# Band_Pass_Filter.net
KiCad netlist of a schematic drawn in Altium Designer
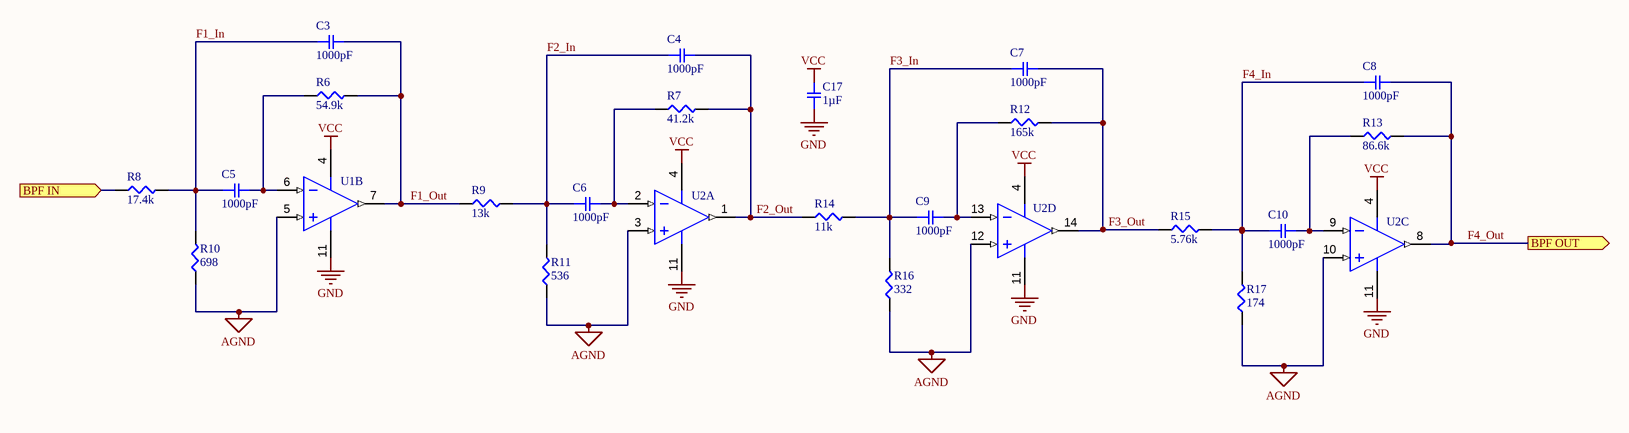
[diagram p0: Band Pass Filter.SchDoc]

(export (version "E")
  (design (tool "Eeschema 10.0.6"))
  (components
    (comp (ref "C3")
      (value "1000pF")
      (footprint "SMD-0603C")
      (description "CAP CER 1000PF 50V X7R 0603")
      (fields
        (field (name "MANUFACTURER") "Walsin Technology Corporation")
        (field (name "MANUFACTURER PART NUMBER") "0603N102F500CT")
      )
      (libsource (lib "capacitor_murata_0603") (part "GCJ188R71H102KA01D"))
    )
    (comp (ref "C4")
      (value "1000pF")
      (footprint "SMD-0603C")
      (description "CAP CER 1000PF 50V X7R 0603")
      (fields
        (field (name "MANUFACTURER") "Walsin Technology Corporation")
        (field (name "MANUFACTURER PART NUMBER") "0603N102F500CT")
      )
      (libsource (lib "capacitor_murata_0603") (part "GCJ188R71H102KA01D"))
    )
    (comp (ref "C5")
      (value "1000pF")
      (footprint "SMD-0603C")
      (description "CAP CER 1000PF 50V X7R 0603")
      (fields
        (field (name "MANUFACTURER") "Walsin Technology Corporation")
        (field (name "MANUFACTURER PART NUMBER") "0603N102F500CT")
      )
      (libsource (lib "capacitor_murata_0603") (part "GCJ188R71H102KA01D"))
    )
    (comp (ref "C6")
      (value "1000pF")
      (footprint "SMD-0603C")
      (description "CAP CER 1000PF 50V X7R 0603")
      (fields
        (field (name "MANUFACTURER") "Walsin Technology Corporation")
        (field (name "MANUFACTURER PART NUMBER") "0603N102F500CT")
      )
      (libsource (lib "capacitor_murata_0603") (part "GCJ188R71H102KA01D"))
    )
    (comp (ref "C7")
      (value "1000pF")
      (footprint "SMD-0603C")
      (description "CAP CER 1000PF 50V X7R 0603")
      (fields
        (field (name "MANUFACTURER") "Walsin Technology Corporation")
        (field (name "MANUFACTURER PART NUMBER") "0603N102F500CT")
      )
      (libsource (lib "capacitor_murata_0603") (part "GCJ188R71H102KA01D"))
    )
    (comp (ref "C8")
      (value "1000pF")
      (footprint "SMD-0603C")
      (description "CAP CER 1000PF 50V X7R 0603")
      (fields
        (field (name "MANUFACTURER") "Walsin Technology Corporation")
        (field (name "MANUFACTURER PART NUMBER") "0603N102F500CT")
      )
      (libsource (lib "capacitor_murata_0603") (part "GCJ188R71H102KA01D"))
    )
    (comp (ref "C9")
      (value "1000pF")
      (footprint "SMD-0603C")
      (description "CAP CER 1000PF 50V X7R 0603")
      (fields
        (field (name "MANUFACTURER") "Walsin Technology Corporation")
        (field (name "MANUFACTURER PART NUMBER") "0603N102F500CT")
      )
      (libsource (lib "capacitor_murata_0603") (part "GCJ188R71H102KA01D"))
    )
    (comp (ref "C10")
      (value "1000pF")
      (footprint "SMD-0603C")
      (description "CAP CER 1000PF 50V X7R 0603")
      (fields
        (field (name "MANUFACTURER") "Walsin Technology Corporation")
        (field (name "MANUFACTURER PART NUMBER") "0603N102F500CT")
      )
      (libsource (lib "capacitor_murata_0603") (part "GCJ188R71H102KA01D"))
    )
    (comp (ref "C17")
      (value "1µF")
      (footprint "SMD-0603C")
      (description "CAP CER 1UF 16V X7R 0603")
      (fields
        (field (name "MANUFACTURER") "Samsung Electro-Mechanics")
        (field (name "MANUFACTURER PART NUMBER") "CL10A105KA8NNNC")
      )
      (libsource (lib "capacitor_murata_0603") (part "GCM188R71C105KA64D"))
    )
    (comp (ref "R6")
      (value "54.9k")
      (footprint "SMD-0603-RES")
      (description "RES SMD 54.9K OHM 1% 1/10W 0603")
      (fields
        (field (name "MANUFACTURER") "Panasonic Electronic Components")
        (field (name "MANUFACTURER PART NUMBER") "ERJ-3EKF5492V")
      )
      (libsource (lib "Panasonic_resistor_0603") (part "ERJ-3EKF5492V"))
    )
    (comp (ref "R7")
      (value "41.2k")
      (footprint "SMD-0603-RES")
      (description "RES SMD 41.2K OHM 1% 1/10W 0603")
      (fields
        (field (name "MANUFACTURER") "Panasonic Electronic Components")
        (field (name "MANUFACTURER PART NUMBER") "ERJ-3EKF4122V")
      )
      (libsource (lib "Panasonic_resistor_0603") (part "ERJ-3EKF4122V"))
    )
    (comp (ref "R8")
      (value "17.4k")
      (footprint "SMD-0603-RES")
      (description "RES SMD 17.4K OHM 1% 1/10W 0603")
      (fields
        (field (name "MANUFACTURER") "Panasonic Electronic Components")
        (field (name "MANUFACTURER PART NUMBER") "ERJ-3EKF1742V")
      )
      (libsource (lib "Panasonic_resistor_0603") (part "ERJ-3EKF1742V"))
    )
    (comp (ref "R9")
      (value "13k")
      (footprint "SMD-0603-RES")
      (description "RES SMD 13K OHM 1% 1/10W 0603")
      (fields
        (field (name "MANUFACTURER") "Panasonic Electronic Components")
        (field (name "MANUFACTURER PART NUMBER") "ERJ-3EKF1302V")
      )
      (libsource (lib "Panasonic_resistor_0603") (part "ERJ-3EKF1302V"))
    )
    (comp (ref "R10")
      (value "698")
      (footprint "SMD-0603-RES")
      (description "RES SMD 698 OHM 1% 1/10W 0603")
      (fields
        (field (name "MANUFACTURER") "Panasonic Electronic Components")
        (field (name "MANUFACTURER PART NUMBER") "ERJ-3EKF6980V")
      )
      (libsource (lib "Panasonic_resistor_0603") (part "ERJ-3EKF6980V"))
    )
    (comp (ref "R11")
      (value "536")
      (footprint "SMD-0603-RES")
      (description "RES SMD 536 OHM 1% 1/10W 0603")
      (fields
        (field (name "MANUFACTURER") "Panasonic Electronic Components")
        (field (name "MANUFACTURER PART NUMBER") "ERJ-3EKF5360V")
      )
      (libsource (lib "Panasonic_resistor_0603") (part "ERJ-3EKF5360V"))
    )
    (comp (ref "R12")
      (value "165k")
      (footprint "SMD-0603-RES")
      (description "RES SMD 165K OHM 1% 1/10W 0603")
      (fields
        (field (name "MANUFACTURER") "Panasonic Electronic Components")
        (field (name "MANUFACTURER PART NUMBER") "ERJ-3EKF1653V")
      )
      (libsource (lib "Panasonic_resistor_0603") (part "ERJ-3EKF1653V"))
    )
    (comp (ref "R13")
      (value "86.6k")
      (footprint "SMD-0603-RES")
      (description "RES SMD 86.6K OHM 1% 1/10W 0603")
      (fields
        (field (name "MANUFACTURER") "Panasonic Electronic Components")
        (field (name "MANUFACTURER PART NUMBER") "ERJ-3EKF8662V")
      )
      (libsource (lib "Panasonic_resistor_0603") (part "ERJ-3EKF8662V"))
    )
    (comp (ref "R14")
      (value "11k")
      (footprint "SMD-0603-RES")
      (description "RES SMD 11K OHM 1% 1/10W 0603")
      (fields
        (field (name "MANUFACTURER") "Panasonic Electronic Components")
        (field (name "MANUFACTURER PART NUMBER") "ERJ-3EKF1102V")
      )
      (libsource (lib "Panasonic_resistor_0603") (part "ERJ-3EKF1102V"))
    )
    (comp (ref "R15")
      (value "5.76k")
      (footprint "SMD-0603-RES")
      (description "RES SMD 5.76K OHM 1% 1/10W 0603")
      (fields
        (field (name "MANUFACTURER") "Panasonic Electronic Components")
        (field (name "MANUFACTURER PART NUMBER") "ERJ-3EKF5761V")
      )
      (libsource (lib "Panasonic_resistor_0603") (part "ERJ-3EKF5761V"))
    )
    (comp (ref "R16")
      (value "332")
      (footprint "SMD-0603-RES")
      (description "RES SMD 332 OHM 1% 1/10W 0603")
      (fields
        (field (name "MANUFACTURER") "Panasonic Electronic Components")
        (field (name "MANUFACTURER PART NUMBER") "ERJ-3EKF3320V")
      )
      (libsource (lib "Panasonic_resistor_0603") (part "ERJ-3EKF3320V"))
    )
    (comp (ref "R17")
      (value "174")
      (footprint "SMD-0603-RES")
      (description "RES SMD 174 OHM 1% 1/10W 0603")
      (fields
        (field (name "MANUFACTURER") "Panasonic Electronic Components")
        (field (name "MANUFACTURER PART NUMBER") "ERJ-3EKF1740V")
      )
      (libsource (lib "Panasonic_resistor_0603") (part "ERJ-3EKF1740V"))
    )
    (comp (ref "U1")
      (value "OPA1604AIPWR")
      (footprint "PW0014A_N")
      (fields (field (name "MANUFACTURER") "Texas Instruments"))
      (libsource (lib "Altium Content Vault") (part "TI-OPA16X4_4XXX-14"))
    )
    (comp (ref "U2")
      (value "OPA1604AIPWR")
      (footprint "PW0014A_N")
      (fields (field (name "MANUFACTURER") "Texas Instruments"))
      (libsource (lib "Altium Content Vault") (part "TI-OPA16X4_4XXX-14"))
    )
  )
  (nets
    (net (code "1") (name "/BPF IN") (class "Default")
      (node (ref "R8") (pin "1") (pinfunction "1_1") (pintype "passive"))
    )
    (net (code "2") (name "/F1_In") (class "Default")
      (node (ref "C3") (pin "1") (pinfunction "1_1") (pintype "passive"))
      (node (ref "C5") (pin "1") (pinfunction "1_1") (pintype "passive"))
      (node (ref "R10") (pin "2") (pinfunction "2_2") (pintype "passive"))
      (node (ref "R8") (pin "2") (pinfunction "2_2") (pintype "passive"))
    )
    (net (code "3") (name "/F1_Out") (class "Default")
      (node (ref "C3") (pin "2") (pinfunction "2_2") (pintype "passive"))
      (node (ref "R6") (pin "2") (pinfunction "2_2") (pintype "passive"))
      (node (ref "R9") (pin "1") (pinfunction "1_1") (pintype "passive"))
      (node (ref "U1") (pin "7") (pinfunction "OUT_B_7") (pintype "output"))
    )
    (net (code "4") (name "/F2_In") (class "Default")
      (node (ref "C4") (pin "1") (pinfunction "1_1") (pintype "passive"))
      (node (ref "C6") (pin "1") (pinfunction "1_1") (pintype "passive"))
      (node (ref "R11") (pin "2") (pinfunction "2_2") (pintype "passive"))
      (node (ref "R9") (pin "2") (pinfunction "2_2") (pintype "passive"))
    )
    (net (code "5") (name "/F2_Out") (class "Default")
      (node (ref "C4") (pin "2") (pinfunction "2_2") (pintype "passive"))
      (node (ref "R14") (pin "1") (pinfunction "1_1") (pintype "passive"))
      (node (ref "R7") (pin "2") (pinfunction "2_2") (pintype "passive"))
      (node (ref "U2") (pin "1") (pinfunction "OUT_A_1") (pintype "output"))
    )
    (net (code "6") (name "/F3_In") (class "Default")
      (node (ref "C7") (pin "1") (pinfunction "1_1") (pintype "passive"))
      (node (ref "C9") (pin "1") (pinfunction "1_1") (pintype "passive"))
      (node (ref "R14") (pin "2") (pinfunction "2_2") (pintype "passive"))
      (node (ref "R16") (pin "2") (pinfunction "2_2") (pintype "passive"))
    )
    (net (code "7") (name "/F3_Out") (class "Default")
      (node (ref "C7") (pin "2") (pinfunction "2_2") (pintype "passive"))
      (node (ref "R12") (pin "2") (pinfunction "2_2") (pintype "passive"))
      (node (ref "R15") (pin "1") (pinfunction "1_1") (pintype "passive"))
      (node (ref "U2") (pin "14") (pinfunction "OUT_D_14") (pintype "output"))
    )
    (net (code "8") (name "/F4_In") (class "Default")
      (node (ref "C10") (pin "1") (pinfunction "1_1") (pintype "passive"))
      (node (ref "C8") (pin "1") (pinfunction "1_1") (pintype "passive"))
      (node (ref "R15") (pin "2") (pinfunction "2_2") (pintype "passive"))
      (node (ref "R17") (pin "2") (pinfunction "2_2") (pintype "passive"))
    )
    (net (code "9") (name "/F4_Out") (class "Default")
      (node (ref "C8") (pin "2") (pinfunction "2_2") (pintype "passive"))
      (node (ref "R13") (pin "2") (pinfunction "2_2") (pintype "passive"))
      (node (ref "U2") (pin "8") (pinfunction "OUT_C_8") (pintype "output"))
    )
    (net (code "10") (name "AGND") (class "Default")
      (node (ref "R10") (pin "1") (pinfunction "1_1") (pintype "passive"))
      (node (ref "R11") (pin "1") (pinfunction "1_1") (pintype "passive"))
      (node (ref "R16") (pin "1") (pinfunction "1_1") (pintype "passive"))
      (node (ref "R17") (pin "1") (pinfunction "1_1") (pintype "passive"))
      (node (ref "U1") (pin "5") (pinfunction "IN_B+_5") (pintype "input"))
      (node (ref "U2") (pin "10") (pinfunction "IN_C+_10") (pintype "input"))
      (node (ref "U2") (pin "12") (pinfunction "IN_D+_12") (pintype "input"))
      (node (ref "U2") (pin "3") (pinfunction "IN_A+_3") (pintype "input"))
    )
    (net (code "11") (name "GND") (class "Default")
      (node (ref "C17") (pin "1") (pinfunction "1_1") (pintype "passive"))
      (node (ref "U1") (pin "11") (pinfunction "V-_11") (pintype "power_in"))
      (node (ref "U2") (pin "11") (pinfunction "V-_11") (pintype "power_in"))
    )
    (net (code "12") (name "Net-(U1B-IN_B-)") (class "Default")
      (node (ref "C5") (pin "2") (pinfunction "2_2") (pintype "passive"))
      (node (ref "R6") (pin "1") (pinfunction "1_1") (pintype "passive"))
      (node (ref "U1") (pin "6") (pinfunction "IN_B-_6") (pintype "input"))
    )
    (net (code "13") (name "Net-(U2A-IN_A-)") (class "Default")
      (node (ref "C6") (pin "2") (pinfunction "2_2") (pintype "passive"))
      (node (ref "R7") (pin "1") (pinfunction "1_1") (pintype "passive"))
      (node (ref "U2") (pin "2") (pinfunction "IN_A-_2") (pintype "input"))
    )
    (net (code "14") (name "Net-(U2C-IN_C-)") (class "Default")
      (node (ref "C10") (pin "2") (pinfunction "2_2") (pintype "passive"))
      (node (ref "R13") (pin "1") (pinfunction "1_1") (pintype "passive"))
      (node (ref "U2") (pin "9") (pinfunction "IN_C-_9") (pintype "input"))
    )
    (net (code "15") (name "Net-(U2D-IN_D-)") (class "Default")
      (node (ref "C9") (pin "2") (pinfunction "2_2") (pintype "passive"))
      (node (ref "R12") (pin "1") (pinfunction "1_1") (pintype "passive"))
      (node (ref "U2") (pin "13") (pinfunction "IN_D-_13") (pintype "input"))
    )
    (net (code "16") (name "VCC") (class "Default")
      (node (ref "C17") (pin "2") (pinfunction "2_2") (pintype "passive"))
      (node (ref "U1") (pin "4") (pinfunction "V+_4") (pintype "power_in"))
      (node (ref "U2") (pin "4") (pinfunction "V+_4") (pintype "power_in"))
    )
  )
)
